# stm32.net
KiCad netlist of a schematic drawn in EAGLE
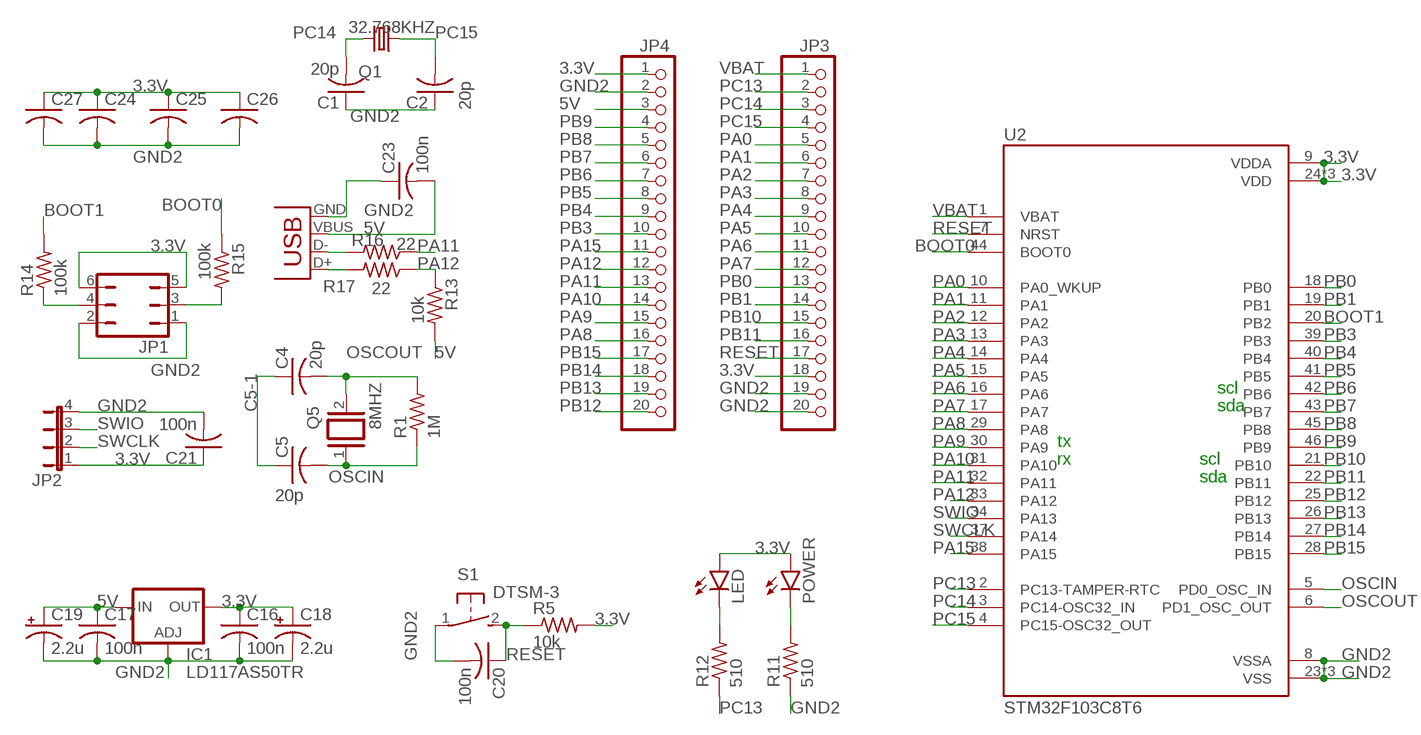
[diagram p0: schematic, sheet 1]

(export (version "E")
  (design (tool "Eeschema 10.0.6"))
  (components
    (comp (ref "C1")
      (value "20p")
      (footprint "eagle-import:C1206")
      (libsource (lib "eagle-import") (part "C-USC1206"))
    )
    (comp (ref "C2")
      (value "20p")
      (footprint "eagle-import:C1206")
      (libsource (lib "eagle-import") (part "C-USC1206"))
    )
    (comp (ref "C4")
      (value "20p")
      (footprint "eagle-import:C1206")
      (libsource (lib "eagle-import") (part "C-USC1206"))
    )
    (comp (ref "C5")
      (value "20p")
      (footprint "eagle-import:C1206")
      (libsource (lib "eagle-import") (part "C-USC1206"))
    )
    (comp (ref "C16")
      (value "100n")
      (footprint "eagle-import:C1206")
      (libsource (lib "eagle-import") (part "C-USC1206"))
    )
    (comp (ref "C17")
      (value "100n")
      (footprint "eagle-import:C1206")
      (libsource (lib "eagle-import") (part "C-USC1206"))
    )
    (comp (ref "C18")
      (value "2.2u")
      (footprint "eagle-import:E2-5")
      (libsource (lib "eagle-import") (part "CPOL-USE2-5"))
    )
    (comp (ref "C19")
      (value "2.2u")
      (footprint "eagle-import:E2-5")
      (libsource (lib "eagle-import") (part "CPOL-USE2-5"))
    )
    (comp (ref "C20")
      (value "100n")
      (footprint "eagle-import:C1206")
      (libsource (lib "eagle-import") (part "C-USC1206"))
    )
    (comp (ref "C21")
      (value "100n")
      (footprint "eagle-import:C1206")
      (libsource (lib "eagle-import") (part "C-USC1206"))
    )
    (comp (ref "C23")
      (value "100n")
      (footprint "eagle-import:C1206")
      (libsource (lib "eagle-import") (part "C-USC1206"))
    )
    (comp (ref "C24")
      (value "C-USC1206")
      (footprint "eagle-import:C1206")
      (libsource (lib "eagle-import") (part "C-USC1206"))
    )
    (comp (ref "C25")
      (value "C-USC1206")
      (footprint "eagle-import:C1206")
      (libsource (lib "eagle-import") (part "C-USC1206"))
    )
    (comp (ref "C26")
      (value "C-USC1206")
      (footprint "eagle-import:C1206")
      (libsource (lib "eagle-import") (part "C-USC1206"))
    )
    (comp (ref "C27")
      (value "C-USC1206")
      (footprint "eagle-import:C1206")
      (libsource (lib "eagle-import") (part "C-USC1206"))
    )
    (comp (ref "IC1")
      (value "LD117AS50TR")
      (footprint "eagle-import:SOT223")
      (libsource (lib "eagle-import") (part "LD117A?S50TR"))
    )
    (comp (ref "JP1")
      (value "JP3Q")
      (footprint "eagle-import:JP3Q")
      (libsource (lib "eagle-import") (part "JP3Q"))
    )
    (comp (ref "JP2")
      (value "JP4E")
      (footprint "eagle-import:JP4")
      (libsource (lib "eagle-import") (part "JP4E"))
    )
    (comp (ref "JP3")
      (value "PINHD-1X20")
      (footprint "eagle-import:1X20")
      (libsource (lib "eagle-import") (part "PINHD-1X20"))
    )
    (comp (ref "JP4")
      (value "PINHD-1X20")
      (footprint "eagle-import:1X20")
      (libsource (lib "eagle-import") (part "PINHD-1X20"))
    )
    (comp (ref "LED")
      (value "LEDCHIPLED_1206")
      (footprint "eagle-import:CHIPLED_1206")
      (libsource (lib "eagle-import") (part "LEDCHIPLED_1206"))
    )
    (comp (ref "POWER")
      (value "LEDCHIPLED_1206")
      (footprint "eagle-import:CHIPLED_1206")
      (libsource (lib "eagle-import") (part "LEDCHIPLED_1206"))
    )
    (comp (ref "Q1")
      (value "32.768KHZ")
      (footprint "eagle-import:TC26H")
      (libsource (lib "eagle-import") (part "CRYSTALTC26H"))
    )
    (comp (ref "Q5")
      (value "8MHZ")
      (footprint "eagle-import:QS")
      (libsource (lib "eagle-import") (part "XTAL/S"))
    )
    (comp (ref "R1")
      (value "1M")
      (footprint "eagle-import:R1206")
      (libsource (lib "eagle-import") (part "R-US_R1206"))
    )
    (comp (ref "R5")
      (value "10k")
      (footprint "eagle-import:R1206")
      (libsource (lib "eagle-import") (part "R-US_R1206"))
    )
    (comp (ref "R11")
      (value "510")
      (footprint "eagle-import:R1206")
      (libsource (lib "eagle-import") (part "R-US_R1206"))
    )
    (comp (ref "R12")
      (value "510")
      (footprint "eagle-import:R1206")
      (libsource (lib "eagle-import") (part "R-US_R1206"))
    )
    (comp (ref "R13")
      (value "10k")
      (footprint "eagle-import:R1206")
      (libsource (lib "eagle-import") (part "R-US_R1206"))
    )
    (comp (ref "R14")
      (value "100k")
      (footprint "eagle-import:R1206")
      (libsource (lib "eagle-import") (part "R-US_R1206"))
    )
    (comp (ref "R15")
      (value "100k")
      (footprint "eagle-import:R1206")
      (libsource (lib "eagle-import") (part "R-US_R1206"))
    )
    (comp (ref "R16")
      (value "22")
      (footprint "eagle-import:R1206")
      (libsource (lib "eagle-import") (part "R-US_R1206"))
    )
    (comp (ref "R17")
      (value "22")
      (footprint "eagle-import:R1206")
      (libsource (lib "eagle-import") (part "R-US_R1206"))
    )
    (comp (ref "S1")
      (value "DTSM-3")
      (footprint "eagle-import:DTSM-3")
      (libsource (lib "eagle-import") (part "DTSM-3"))
    )
    (comp (ref "U2")
      (value "STM32F103C8T6")
      (footprint "eagle-import:QFP50P900X900X160-48N")
      (fields (field (name "MF") "STMicroelectronics"))
      (libsource (lib "eagle-import") (part "STM32F103C8T6"))
    )
    (comp (ref "X1")
      (value "USB-MB-S")
      (footprint "eagle-import:USB-MB-S")
      (libsource (lib "eagle-import") (part "USB-MB-S"))
    )
  )
  (nets
    (net (code "1") (name "/3.3V") (class "Default")
      (node (ref "C16") (pin "1") (pinfunction "1_1") (pintype "passive"))
      (node (ref "C18") (pin "+") (pinfunction "+_+") (pintype "passive"))
      (node (ref "C21") (pin "1") (pinfunction "1_1") (pintype "passive"))
      (node (ref "C24") (pin "1") (pinfunction "1_1") (pintype "passive"))
      (node (ref "C25") (pin "1") (pinfunction "1_1") (pintype "passive"))
      (node (ref "C26") (pin "1") (pinfunction "1_1") (pintype "passive"))
      (node (ref "C27") (pin "1") (pinfunction "1_1") (pintype "passive"))
      (node (ref "IC1") (pin "4") (pinfunction "OUT_4") (pintype "passive"))
      (node (ref "JP1") (pin "5") (pinfunction "5_5") (pintype "passive"))
      (node (ref "JP1") (pin "6") (pinfunction "6_6") (pintype "passive"))
      (node (ref "JP2") (pin "1") (pinfunction "1_1") (pintype "passive"))
      (node (ref "JP3") (pin "18") (pinfunction "18_18") (pintype "passive"))
      (node (ref "JP4") (pin "1") (pinfunction "1_1") (pintype "passive"))
      (node (ref "LED") (pin "A") (pinfunction "A_A") (pintype "passive"))
      (node (ref "POWER") (pin "A") (pinfunction "A_A") (pintype "passive"))
      (node (ref "R5") (pin "2") (pinfunction "2_2") (pintype "passive"))
      (node (ref "U2") (pin "24") (pinfunction "VDD_24") (pintype "power_in"))
      (node (ref "U2") (pin "36") (pinfunction "VDD_36") (pintype "power_in"))
      (node (ref "U2") (pin "48") (pinfunction "VDD_48") (pintype "power_in"))
      (node (ref "U2") (pin "9") (pinfunction "VDDA_9") (pintype "power_in"))
    )
    (net (code "2") (name "/5V") (class "Default")
      (node (ref "C17") (pin "1") (pinfunction "1_1") (pintype "passive"))
      (node (ref "C19") (pin "+") (pinfunction "+_+") (pintype "passive"))
      (node (ref "C23") (pin "2") (pinfunction "2_2") (pintype "passive"))
      (node (ref "IC1") (pin "3") (pinfunction "IN_3") (pintype "input"))
      (node (ref "JP4") (pin "3") (pinfunction "3_3") (pintype "passive"))
      (node (ref "R13") (pin "2") (pinfunction "2_2") (pintype "passive"))
      (node (ref "X1") (pin "VBUS") (pinfunction "VBUS_VBUS") (pintype "bidirectional"))
    )
    (net (code "3") (name "/BOOT0") (class "Default")
      (node (ref "R15") (pin "1") (pinfunction "1_1") (pintype "passive"))
      (node (ref "U2") (pin "44") (pinfunction "BOOT0_44") (pintype "input"))
    )
    (net (code "4") (name "/BOOT1") (class "Default")
      (node (ref "R14") (pin "2") (pinfunction "2_2") (pintype "passive"))
      (node (ref "U2") (pin "20") (pinfunction "PB2_20") (pintype "bidirectional"))
    )
    (net (code "5") (name "/C5-1") (class "Default")
      (node (ref "C4") (pin "1") (pinfunction "1_1") (pintype "passive"))
      (node (ref "C5") (pin "1") (pinfunction "1_1") (pintype "passive"))
    )
    (net (code "6") (name "/GND2") (class "Default")
      (node (ref "C1") (pin "1") (pinfunction "1_1") (pintype "passive"))
      (node (ref "C16") (pin "2") (pinfunction "2_2") (pintype "passive"))
      (node (ref "C17") (pin "2") (pinfunction "2_2") (pintype "passive"))
      (node (ref "C18") (pin "-") (pinfunction "-_-") (pintype "passive"))
      (node (ref "C19") (pin "-") (pinfunction "-_-") (pintype "passive"))
      (node (ref "C2") (pin "1") (pinfunction "1_1") (pintype "passive"))
      (node (ref "C20") (pin "2") (pinfunction "2_2") (pintype "passive"))
      (node (ref "C21") (pin "2") (pinfunction "2_2") (pintype "passive"))
      (node (ref "C23") (pin "1") (pinfunction "1_1") (pintype "passive"))
      (node (ref "C24") (pin "2") (pinfunction "2_2") (pintype "passive"))
      (node (ref "C25") (pin "2") (pinfunction "2_2") (pintype "passive"))
      (node (ref "C26") (pin "2") (pinfunction "2_2") (pintype "passive"))
      (node (ref "C27") (pin "2") (pinfunction "2_2") (pintype "passive"))
      (node (ref "IC1") (pin "1") (pinfunction "ADJ_1") (pintype "input"))
      (node (ref "JP1") (pin "1") (pinfunction "1_1") (pintype "passive"))
      (node (ref "JP1") (pin "2") (pinfunction "2_2") (pintype "passive"))
      (node (ref "JP2") (pin "4") (pinfunction "4_4") (pintype "passive"))
      (node (ref "JP3") (pin "19") (pinfunction "19_19") (pintype "passive"))
      (node (ref "JP3") (pin "20") (pinfunction "20_20") (pintype "passive"))
      (node (ref "JP4") (pin "2") (pinfunction "2_2") (pintype "passive"))
      (node (ref "R11") (pin "1") (pinfunction "1_1") (pintype "passive"))
      (node (ref "S1") (pin "1") (pinfunction "1_1") (pintype "passive"))
      (node (ref "U2") (pin "23") (pinfunction "VSS_23") (pintype "power_in"))
      (node (ref "U2") (pin "35") (pinfunction "VSS_35") (pintype "power_in"))
      (node (ref "U2") (pin "47") (pinfunction "VSS_47") (pintype "power_in"))
      (node (ref "U2") (pin "8") (pinfunction "VSSA_8") (pintype "power_in"))
      (node (ref "X1") (pin "GND") (pinfunction "GND_GND") (pintype "bidirectional"))
    )
    (net (code "7") (name "/OSCIN") (class "Default")
      (node (ref "C5") (pin "2") (pinfunction "2_2") (pintype "passive"))
      (node (ref "Q5") (pin "1") (pinfunction "1_1") (pintype "passive"))
      (node (ref "R1") (pin "1") (pinfunction "1_1") (pintype "passive"))
      (node (ref "U2") (pin "5") (pinfunction "PD0_OSC_IN_5") (pintype "bidirectional"))
    )
    (net (code "8") (name "/OSCOUT") (class "Default")
      (node (ref "C4") (pin "2") (pinfunction "2_2") (pintype "passive"))
      (node (ref "Q5") (pin "2") (pinfunction "2_2") (pintype "passive"))
      (node (ref "R1") (pin "2") (pinfunction "2_2") (pintype "passive"))
      (node (ref "U2") (pin "6") (pinfunction "PD1_OSC_OUT_6") (pintype "bidirectional"))
    )
    (net (code "9") (name "/PA0") (class "Default")
      (node (ref "JP3") (pin "5") (pinfunction "5_5") (pintype "passive"))
      (node (ref "U2") (pin "10") (pinfunction "PA0_WKUP_10") (pintype "bidirectional"))
    )
    (net (code "10") (name "/PA1") (class "Default")
      (node (ref "JP3") (pin "6") (pinfunction "6_6") (pintype "passive"))
      (node (ref "U2") (pin "11") (pinfunction "PA1_11") (pintype "bidirectional"))
    )
    (net (code "11") (name "/PA2") (class "Default")
      (node (ref "JP3") (pin "7") (pinfunction "7_7") (pintype "passive"))
      (node (ref "U2") (pin "12") (pinfunction "PA2_12") (pintype "bidirectional"))
    )
    (net (code "12") (name "/PA3") (class "Default")
      (node (ref "JP3") (pin "8") (pinfunction "8_8") (pintype "passive"))
      (node (ref "U2") (pin "13") (pinfunction "PA3_13") (pintype "bidirectional"))
    )
    (net (code "13") (name "/PA4") (class "Default")
      (node (ref "JP3") (pin "9") (pinfunction "9_9") (pintype "passive"))
      (node (ref "U2") (pin "14") (pinfunction "PA4_14") (pintype "bidirectional"))
    )
    (net (code "14") (name "/PA5") (class "Default")
      (node (ref "JP3") (pin "10") (pinfunction "10_10") (pintype "passive"))
      (node (ref "U2") (pin "15") (pinfunction "PA5_15") (pintype "bidirectional"))
    )
    (net (code "15") (name "/PA6") (class "Default")
      (node (ref "JP3") (pin "11") (pinfunction "11_11") (pintype "passive"))
      (node (ref "U2") (pin "16") (pinfunction "PA6_16") (pintype "bidirectional"))
    )
    (net (code "16") (name "/PA7") (class "Default")
      (node (ref "JP3") (pin "12") (pinfunction "12_12") (pintype "passive"))
      (node (ref "U2") (pin "17") (pinfunction "PA7_17") (pintype "bidirectional"))
    )
    (net (code "17") (name "/PA8") (class "Default")
      (node (ref "JP4") (pin "16") (pinfunction "16_16") (pintype "passive"))
      (node (ref "U2") (pin "29") (pinfunction "PA8_29") (pintype "bidirectional"))
    )
    (net (code "18") (name "/PA9") (class "Default")
      (node (ref "JP4") (pin "15") (pinfunction "15_15") (pintype "passive"))
      (node (ref "U2") (pin "30") (pinfunction "PA9_30") (pintype "bidirectional"))
    )
    (net (code "19") (name "/PA10") (class "Default")
      (node (ref "JP4") (pin "14") (pinfunction "14_14") (pintype "passive"))
      (node (ref "U2") (pin "31") (pinfunction "PA10_31") (pintype "bidirectional"))
    )
    (net (code "20") (name "/PA11") (class "Default")
      (node (ref "JP4") (pin "13") (pinfunction "13_13") (pintype "passive"))
      (node (ref "R16") (pin "1") (pinfunction "1_1") (pintype "passive"))
      (node (ref "U2") (pin "32") (pinfunction "PA11_32") (pintype "bidirectional"))
    )
    (net (code "21") (name "/PA12") (class "Default")
      (node (ref "JP4") (pin "12") (pinfunction "12_12") (pintype "passive"))
      (node (ref "R13") (pin "1") (pinfunction "1_1") (pintype "passive"))
      (node (ref "R17") (pin "1") (pinfunction "1_1") (pintype "passive"))
      (node (ref "U2") (pin "33") (pinfunction "PA12_33") (pintype "bidirectional"))
    )
    (net (code "22") (name "/PA15") (class "Default")
      (node (ref "JP4") (pin "11") (pinfunction "11_11") (pintype "passive"))
      (node (ref "U2") (pin "38") (pinfunction "PA15_38") (pintype "bidirectional"))
    )
    (net (code "23") (name "/PB0") (class "Default")
      (node (ref "JP3") (pin "13") (pinfunction "13_13") (pintype "passive"))
      (node (ref "U2") (pin "18") (pinfunction "PB0_18") (pintype "bidirectional"))
    )
    (net (code "24") (name "/PB1") (class "Default")
      (node (ref "JP3") (pin "14") (pinfunction "14_14") (pintype "passive"))
      (node (ref "U2") (pin "19") (pinfunction "PB1_19") (pintype "bidirectional"))
    )
    (net (code "25") (name "/PB3") (class "Default")
      (node (ref "JP4") (pin "10") (pinfunction "10_10") (pintype "passive"))
      (node (ref "U2") (pin "39") (pinfunction "PB3_39") (pintype "bidirectional"))
    )
    (net (code "26") (name "/PB4") (class "Default")
      (node (ref "JP4") (pin "9") (pinfunction "9_9") (pintype "passive"))
      (node (ref "U2") (pin "40") (pinfunction "PB4_40") (pintype "bidirectional"))
    )
    (net (code "27") (name "/PB5") (class "Default")
      (node (ref "JP4") (pin "8") (pinfunction "8_8") (pintype "passive"))
      (node (ref "U2") (pin "41") (pinfunction "PB5_41") (pintype "bidirectional"))
    )
    (net (code "28") (name "/PB6") (class "Default")
      (node (ref "JP4") (pin "7") (pinfunction "7_7") (pintype "passive"))
      (node (ref "U2") (pin "42") (pinfunction "PB6_42") (pintype "bidirectional"))
    )
    (net (code "29") (name "/PB7") (class "Default")
      (node (ref "JP4") (pin "6") (pinfunction "6_6") (pintype "passive"))
      (node (ref "U2") (pin "43") (pinfunction "PB7_43") (pintype "bidirectional"))
    )
    (net (code "30") (name "/PB8") (class "Default")
      (node (ref "JP4") (pin "5") (pinfunction "5_5") (pintype "passive"))
      (node (ref "U2") (pin "45") (pinfunction "PB8_45") (pintype "bidirectional"))
    )
    (net (code "31") (name "/PB9") (class "Default")
      (node (ref "JP4") (pin "4") (pinfunction "4_4") (pintype "passive"))
      (node (ref "U2") (pin "46") (pinfunction "PB9_46") (pintype "bidirectional"))
    )
    (net (code "32") (name "/PB10") (class "Default")
      (node (ref "JP3") (pin "15") (pinfunction "15_15") (pintype "passive"))
      (node (ref "U2") (pin "21") (pinfunction "PB10_21") (pintype "bidirectional"))
    )
    (net (code "33") (name "/PB11") (class "Default")
      (node (ref "JP3") (pin "16") (pinfunction "16_16") (pintype "passive"))
      (node (ref "U2") (pin "22") (pinfunction "PB11_22") (pintype "bidirectional"))
    )
    (net (code "34") (name "/PB12") (class "Default")
      (node (ref "JP4") (pin "20") (pinfunction "20_20") (pintype "passive"))
      (node (ref "U2") (pin "25") (pinfunction "PB12_25") (pintype "bidirectional"))
    )
    (net (code "35") (name "/PB13") (class "Default")
      (node (ref "JP4") (pin "19") (pinfunction "19_19") (pintype "passive"))
      (node (ref "U2") (pin "26") (pinfunction "PB13_26") (pintype "bidirectional"))
    )
    (net (code "36") (name "/PB14") (class "Default")
      (node (ref "JP4") (pin "18") (pinfunction "18_18") (pintype "passive"))
      (node (ref "U2") (pin "27") (pinfunction "PB14_27") (pintype "bidirectional"))
    )
    (net (code "37") (name "/PB15") (class "Default")
      (node (ref "JP4") (pin "17") (pinfunction "17_17") (pintype "passive"))
      (node (ref "U2") (pin "28") (pinfunction "PB15_28") (pintype "bidirectional"))
    )
    (net (code "38") (name "/PC13") (class "Default")
      (node (ref "JP3") (pin "2") (pinfunction "2_2") (pintype "passive"))
      (node (ref "R12") (pin "1") (pinfunction "1_1") (pintype "passive"))
      (node (ref "U2") (pin "2") (pinfunction "PC13-TAMPER-RTC_2") (pintype "bidirectional"))
    )
    (net (code "39") (name "/PC14") (class "Default")
      (node (ref "C1") (pin "2") (pinfunction "2_2") (pintype "passive"))
      (node (ref "JP3") (pin "3") (pinfunction "3_3") (pintype "passive"))
      (node (ref "Q1") (pin "2") (pinfunction "2_2") (pintype "passive"))
      (node (ref "U2") (pin "3") (pinfunction "PC14-OSC32_IN_3") (pintype "bidirectional"))
    )
    (net (code "40") (name "/PC15") (class "Default")
      (node (ref "C2") (pin "2") (pinfunction "2_2") (pintype "passive"))
      (node (ref "JP3") (pin "4") (pinfunction "4_4") (pintype "passive"))
      (node (ref "Q1") (pin "1") (pinfunction "1_1") (pintype "passive"))
      (node (ref "U2") (pin "4") (pinfunction "PC15-OSC32_OUT_4") (pintype "bidirectional"))
    )
    (net (code "41") (name "/RESET") (class "Default")
      (node (ref "C20") (pin "1") (pinfunction "1_1") (pintype "passive"))
      (node (ref "JP3") (pin "17") (pinfunction "17_17") (pintype "passive"))
      (node (ref "R5") (pin "1") (pinfunction "1_1") (pintype "passive"))
      (node (ref "S1") (pin "2") (pinfunction "2_2") (pintype "passive"))
      (node (ref "U2") (pin "7") (pinfunction "NRST_7") (pintype "input"))
    )
    (net (code "42") (name "/SWCLK") (class "Default")
      (node (ref "JP2") (pin "2") (pinfunction "2_2") (pintype "passive"))
      (node (ref "U2") (pin "37") (pinfunction "PA14_37") (pintype "bidirectional"))
    )
    (net (code "43") (name "/SWIO") (class "Default")
      (node (ref "JP2") (pin "3") (pinfunction "3_3") (pintype "passive"))
      (node (ref "U2") (pin "34") (pinfunction "PA13_34") (pintype "bidirectional"))
    )
    (net (code "44") (name "/VBAT") (class "Default")
      (node (ref "JP3") (pin "1") (pinfunction "1_1") (pintype "passive"))
      (node (ref "U2") (pin "1") (pinfunction "VBAT_1") (pintype "bidirectional"))
    )
    (net (code "45") (name "Net-(JP1-Pad3)") (class "Default")
      (node (ref "JP1") (pin "3") (pinfunction "3_3") (pintype "passive"))
      (node (ref "R15") (pin "2") (pinfunction "2_2") (pintype "passive"))
    )
    (net (code "46") (name "Net-(JP1-Pad4)") (class "Default")
      (node (ref "JP1") (pin "4") (pinfunction "4_4") (pintype "passive"))
      (node (ref "R14") (pin "1") (pinfunction "1_1") (pintype "passive"))
    )
    (net (code "47") (name "Net-(LED-PadC)") (class "Default")
      (node (ref "LED") (pin "C") (pinfunction "C_C") (pintype "passive"))
      (node (ref "R12") (pin "2") (pinfunction "2_2") (pintype "passive"))
    )
    (net (code "48") (name "Net-(POWER-PadC)") (class "Default")
      (node (ref "POWER") (pin "C") (pinfunction "C_C") (pintype "passive"))
      (node (ref "R11") (pin "2") (pinfunction "2_2") (pintype "passive"))
    )
    (net (code "49") (name "Net-(R16-Pad2)") (class "Default")
      (node (ref "R16") (pin "2") (pinfunction "2_2") (pintype "passive"))
      (node (ref "X1") (pin "D-") (pinfunction "D-_D-") (pintype "bidirectional"))
    )
    (net (code "50") (name "Net-(R17-Pad2)") (class "Default")
      (node (ref "R17") (pin "2") (pinfunction "2_2") (pintype "passive"))
      (node (ref "X1") (pin "D+") (pinfunction "D+_D+") (pintype "bidirectional"))
    )
  )
)
